# FMC_HPC_UFL_DEBUG_TOP.net
KiCad netlist of a schematic drawn in Altium Designer
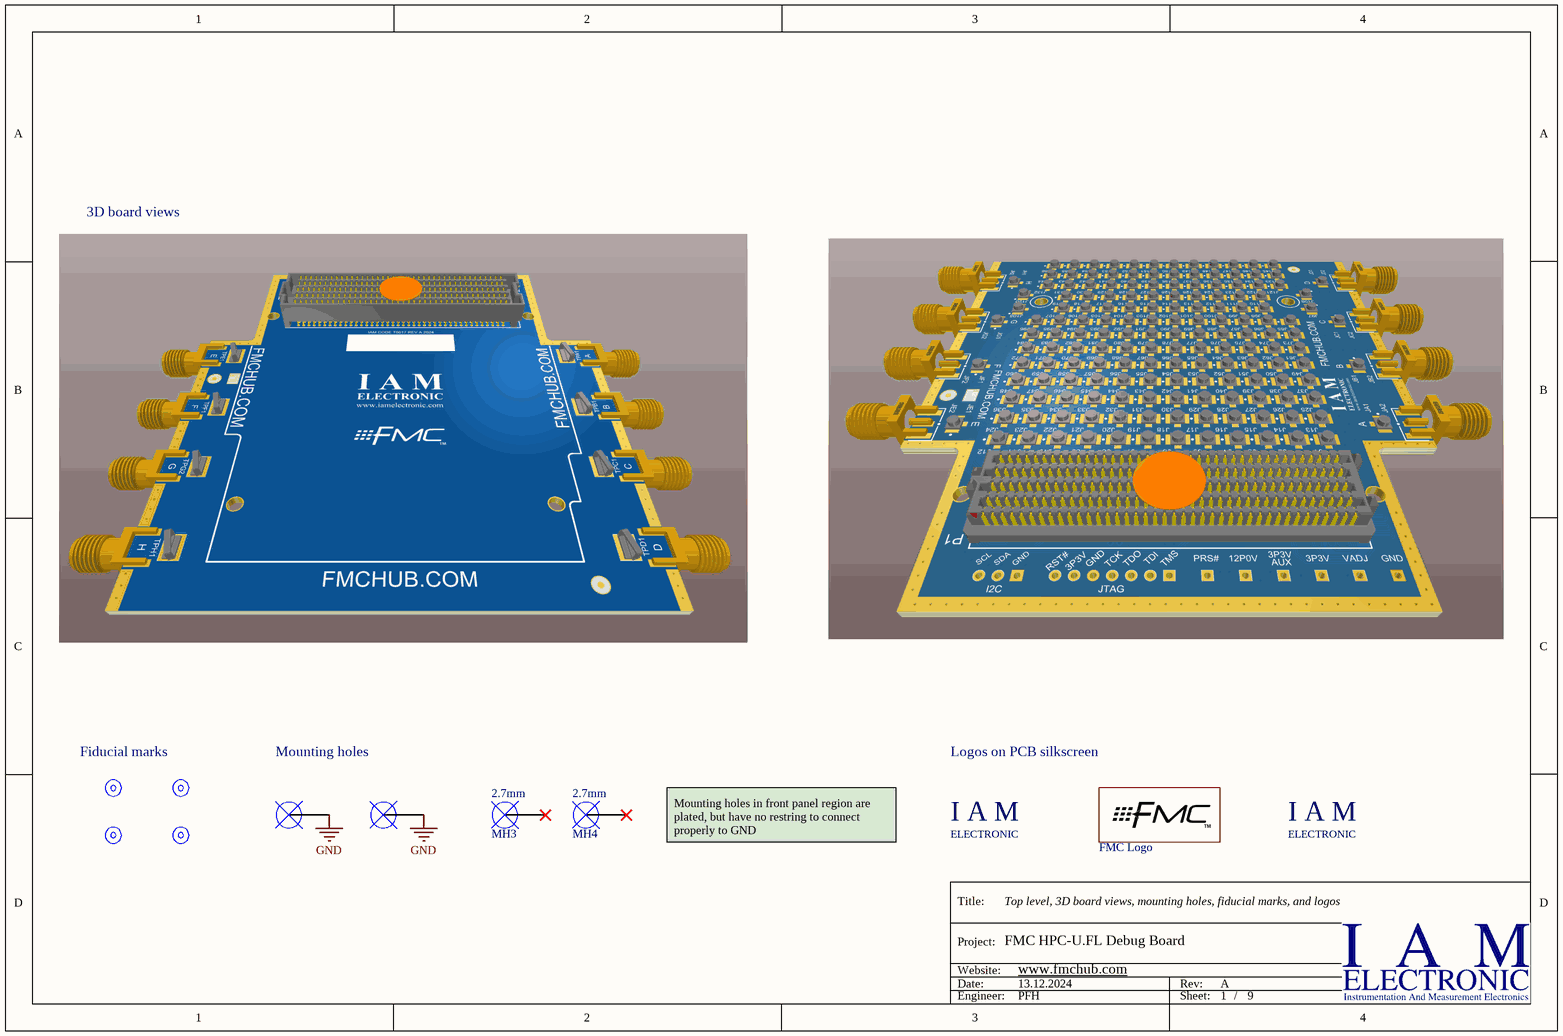
[diagram p0: FMC_HPC_UFL_DEBUG_TOP.SchDoc]

(export (version "E")
  (design (tool "Eeschema 10.0.6"))
  (components
    (comp (ref "FM1")
      (value "1mm")
      (footprint "FIDUCIAL_MARK_ROUND_RING")
      (description "Fiducial mark, width 1mm, clearance 3mm")
      (libsource (lib "VITA_57_FMC") (part "Fiducial_Mark"))
    )
    (comp (ref "FM2")
      (value "1mm")
      (footprint "FIDUCIAL_MARK_ROUND_RING")
      (description "Fiducial mark, width 1mm, clearance 3mm")
      (libsource (lib "VITA_57_FMC") (part "Fiducial_Mark"))
    )
    (comp (ref "FM3")
      (value "1mm")
      (footprint "FIDUCIAL_MARK_ROUND_RING")
      (description "Fiducial mark, width 1mm, clearance 3mm")
      (libsource (lib "VITA_57_FMC") (part "Fiducial_Mark"))
    )
    (comp (ref "FM4")
      (value "1mm")
      (footprint "FIDUCIAL_MARK_ROUND_RING")
      (description "Fiducial mark, width 1mm, clearance 3mm")
      (libsource (lib "VITA_57_FMC") (part "Fiducial_Mark"))
    )
    (comp (ref "MH1")
      (value "2.7mm")
      (footprint "Mounting_Hole_Plated_2.7mm-COVERED")
      (description "Mounting hole, hole size 2.7mm")
      (libsource (lib "VITA_57_FMC") (part "Mounting_Hole_2.7mm"))
    )
    (comp (ref "MH2")
      (value "2.7mm")
      (footprint "Mounting_Hole_Plated_2.7mm-COVERED")
      (description "Mounting hole, hole size 2.7mm")
      (libsource (lib "VITA_57_FMC") (part "Mounting_Hole_2.7mm"))
    )
    (comp (ref "MH3")
      (value "2.7mm")
      (footprint "Mounting_Hole_Plated_2.7mm - d3.1mm")
      (description "Mounting hole, hole size 2.7mm")
      (libsource (lib "VITA_57_FMC") (part "Mounting_Hole_2.7mm"))
    )
    (comp (ref "MH4")
      (value "2.7mm")
      (footprint "Mounting_Hole_Plated_2.7mm - d3.1mm")
      (description "Mounting hole, hole size 2.7mm")
      (libsource (lib "VITA_57_FMC") (part "Mounting_Hole_2.7mm"))
    )
    (comp (ref "STR1")
      (value "IAM LOGO")
      (footprint "IAM LOGO - LARGE - WWW")
      (description "I A M E L E C T R O N I C - Logo")
      (fields (field (name "MANUFACTURER") "IAM ELECTRONIC") (field (name "PART") "Logo"))
      (libsource (lib "IAM_LOGOS") (part "IAM_LOGO"))
    )
    (comp (ref "STR2")
      (value "FMC Logo")
      (footprint "FMC_TM_LOGO_MEDIUM")
      (description "VITA FMC Logo")
      (libsource (lib "VITA_57_FMC") (part "FMC_Logo"))
    )
    (comp (ref "STR3")
      (value "IAM LOGO")
      (footprint "IAM LOGO - SMALL - WWW")
      (description "I A M E L E C T R O N I C - Logo")
      (fields (field (name "MANUFACTURER") "IAM ELECTRONIC") (field (name "PART") "Logo"))
      (libsource (lib "IAM_LOGOS") (part "IAM_LOGO"))
    )
  )
  (nets
    (net (code "1") (name "GND") (class "Default")
      (node (ref "MH1") (pin "0") (pinfunction "0_0") (pintype "passive"))
      (node (ref "MH2") (pin "0") (pinfunction "0_0") (pintype "passive"))
    )
    (net (code "2") (name "unconnected-(FM1-PadFD0)") (class "Default")
      (node (ref "FM1") (pin "FD0") (pinfunction "FD0_FD0") (pintype "passive"))
    )
    (net (code "3") (name "unconnected-(FM2-PadFD0)") (class "Default")
      (node (ref "FM2") (pin "FD0") (pinfunction "FD0_FD0") (pintype "passive"))
    )
    (net (code "4") (name "unconnected-(FM3-PadFD0)") (class "Default")
      (node (ref "FM3") (pin "FD0") (pinfunction "FD0_FD0") (pintype "passive"))
    )
    (net (code "5") (name "unconnected-(FM4-PadFD0)") (class "Default")
      (node (ref "FM4") (pin "FD0") (pinfunction "FD0_FD0") (pintype "passive"))
    )
    (net (code "6") (name "unconnected-(MH3-Pad0)") (class "Default")
      (node (ref "MH3") (pin "0") (pinfunction "0_0") (pintype "passive+no_connect"))
    )
    (net (code "7") (name "unconnected-(MH4-Pad0)") (class "Default")
      (node (ref "MH4") (pin "0") (pinfunction "0_0") (pintype "passive+no_connect"))
    )
  )
)
